# AnalogKeyPad.net
KiCad netlist of a schematic drawn in EAGLE
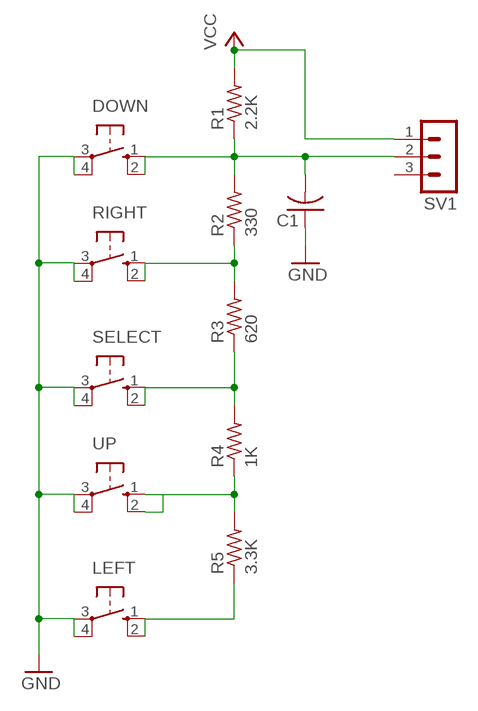
[diagram p0: schematic, sheet 1]

(export (version "E")
  (design (tool "Eeschema 10.0.6"))
  (components
    (comp (ref "C1")
      (value "C-US050-024X044")
      (footprint "eagle-import:C050-024X044")
      (libsource (lib "eagle-import") (part "C-US050-024X044"))
    )
    (comp (ref "DOWN")
      (value "10-XX")
      (footprint "eagle-import:B3F-10XX")
      (fields (field (name "MPN") "B3F-1000"))
      (libsource (lib "eagle-import") (part "10-XX"))
    )
    (comp (ref "LEFT")
      (value "10-XX")
      (footprint "eagle-import:B3F-10XX")
      (fields (field (name "MPN") "B3F-1000"))
      (libsource (lib "eagle-import") (part "10-XX"))
    )
    (comp (ref "R1")
      (value "2.2K")
      (footprint "eagle-import:0207_7")
      (libsource (lib "eagle-import") (part "R-US_0207/7"))
    )
    (comp (ref "R2")
      (value "330")
      (footprint "eagle-import:0207_7")
      (libsource (lib "eagle-import") (part "R-US_0207/7"))
    )
    (comp (ref "R3")
      (value "620")
      (footprint "eagle-import:0207_7")
      (libsource (lib "eagle-import") (part "R-US_0207/7"))
    )
    (comp (ref "R4")
      (value "1K")
      (footprint "eagle-import:0207_7")
      (libsource (lib "eagle-import") (part "R-US_0207/7"))
    )
    (comp (ref "R5")
      (value "3.3K")
      (footprint "eagle-import:0207_7")
      (libsource (lib "eagle-import") (part "R-US_0207/7"))
    )
    (comp (ref "RIGHT")
      (value "10-XX")
      (footprint "eagle-import:B3F-10XX")
      (fields (field (name "MPN") "B3F-1000"))
      (libsource (lib "eagle-import") (part "10-XX"))
    )
    (comp (ref "SELECT")
      (value "10-XX")
      (footprint "eagle-import:B3F-10XX")
      (fields (field (name "MPN") "B3F-1000"))
      (libsource (lib "eagle-import") (part "10-XX"))
    )
    (comp (ref "SV1")
      (value "MA03-1")
      (footprint "eagle-import:MA03-1")
      (libsource (lib "eagle-import") (part "MA03-1"))
    )
    (comp (ref "UP")
      (value "10-XX")
      (footprint "eagle-import:B3F-10XX")
      (fields (field (name "MPN") "B3F-1000"))
      (libsource (lib "eagle-import") (part "10-XX"))
    )
  )
  (nets
    (net (code "1") (name "GND") (class "Default")
      (node (ref "C1") (pin "1") (pinfunction "1_1") (pintype "passive"))
      (node (ref "DOWN") (pin "3") (pinfunction "P_3") (pintype "passive"))
      (node (ref "DOWN") (pin "4") (pinfunction "P1_4") (pintype "passive"))
      (node (ref "LEFT") (pin "3") (pinfunction "P_3") (pintype "passive"))
      (node (ref "LEFT") (pin "4") (pinfunction "P1_4") (pintype "passive"))
      (node (ref "RIGHT") (pin "3") (pinfunction "P_3") (pintype "passive"))
      (node (ref "RIGHT") (pin "4") (pinfunction "P1_4") (pintype "passive"))
      (node (ref "SELECT") (pin "3") (pinfunction "P_3") (pintype "passive"))
      (node (ref "SELECT") (pin "4") (pinfunction "P1_4") (pintype "passive"))
      (node (ref "UP") (pin "3") (pinfunction "P_3") (pintype "passive"))
      (node (ref "UP") (pin "4") (pinfunction "P1_4") (pintype "passive"))
    )
    (net (code "2") (name "Net-(DOWN-S)") (class "Default")
      (node (ref "C1") (pin "2") (pinfunction "2_2") (pintype "passive"))
      (node (ref "DOWN") (pin "1") (pinfunction "S_1") (pintype "passive"))
      (node (ref "DOWN") (pin "2") (pinfunction "S1_2") (pintype "passive"))
      (node (ref "R1") (pin "1") (pinfunction "1_1") (pintype "passive"))
      (node (ref "R2") (pin "2") (pinfunction "2_2") (pintype "passive"))
      (node (ref "SV1") (pin "2") (pinfunction "2_2") (pintype "passive"))
    )
    (net (code "3") (name "Net-(LEFT-S)") (class "Default")
      (node (ref "LEFT") (pin "1") (pinfunction "S_1") (pintype "passive"))
      (node (ref "LEFT") (pin "2") (pinfunction "S1_2") (pintype "passive"))
      (node (ref "R5") (pin "1") (pinfunction "1_1") (pintype "passive"))
    )
    (net (code "4") (name "Net-(RIGHT-S)") (class "Default")
      (node (ref "R2") (pin "1") (pinfunction "1_1") (pintype "passive"))
      (node (ref "R3") (pin "2") (pinfunction "2_2") (pintype "passive"))
      (node (ref "RIGHT") (pin "1") (pinfunction "S_1") (pintype "passive"))
      (node (ref "RIGHT") (pin "2") (pinfunction "S1_2") (pintype "passive"))
    )
    (net (code "5") (name "Net-(SELECT-S)") (class "Default")
      (node (ref "R3") (pin "1") (pinfunction "1_1") (pintype "passive"))
      (node (ref "R4") (pin "2") (pinfunction "2_2") (pintype "passive"))
      (node (ref "SELECT") (pin "1") (pinfunction "S_1") (pintype "passive"))
      (node (ref "SELECT") (pin "2") (pinfunction "S1_2") (pintype "passive"))
    )
    (net (code "6") (name "Net-(UP-S)") (class "Default")
      (node (ref "R4") (pin "1") (pinfunction "1_1") (pintype "passive"))
      (node (ref "R5") (pin "2") (pinfunction "2_2") (pintype "passive"))
      (node (ref "UP") (pin "1") (pinfunction "S_1") (pintype "passive"))
      (node (ref "UP") (pin "2") (pinfunction "S1_2") (pintype "passive"))
    )
    (net (code "7") (name "VCC") (class "Default")
      (node (ref "R1") (pin "2") (pinfunction "2_2") (pintype "passive"))
      (node (ref "SV1") (pin "1") (pinfunction "1_1") (pintype "passive"))
    )
    (net (code "8") (name "unconnected-(SV1-Pad3)") (class "Default")
      (node (ref "SV1") (pin "3") (pinfunction "3_3") (pintype "passive"))
    )
  )
)
